# Main.net
KiCad netlist of a schematic drawn in Altium Designer
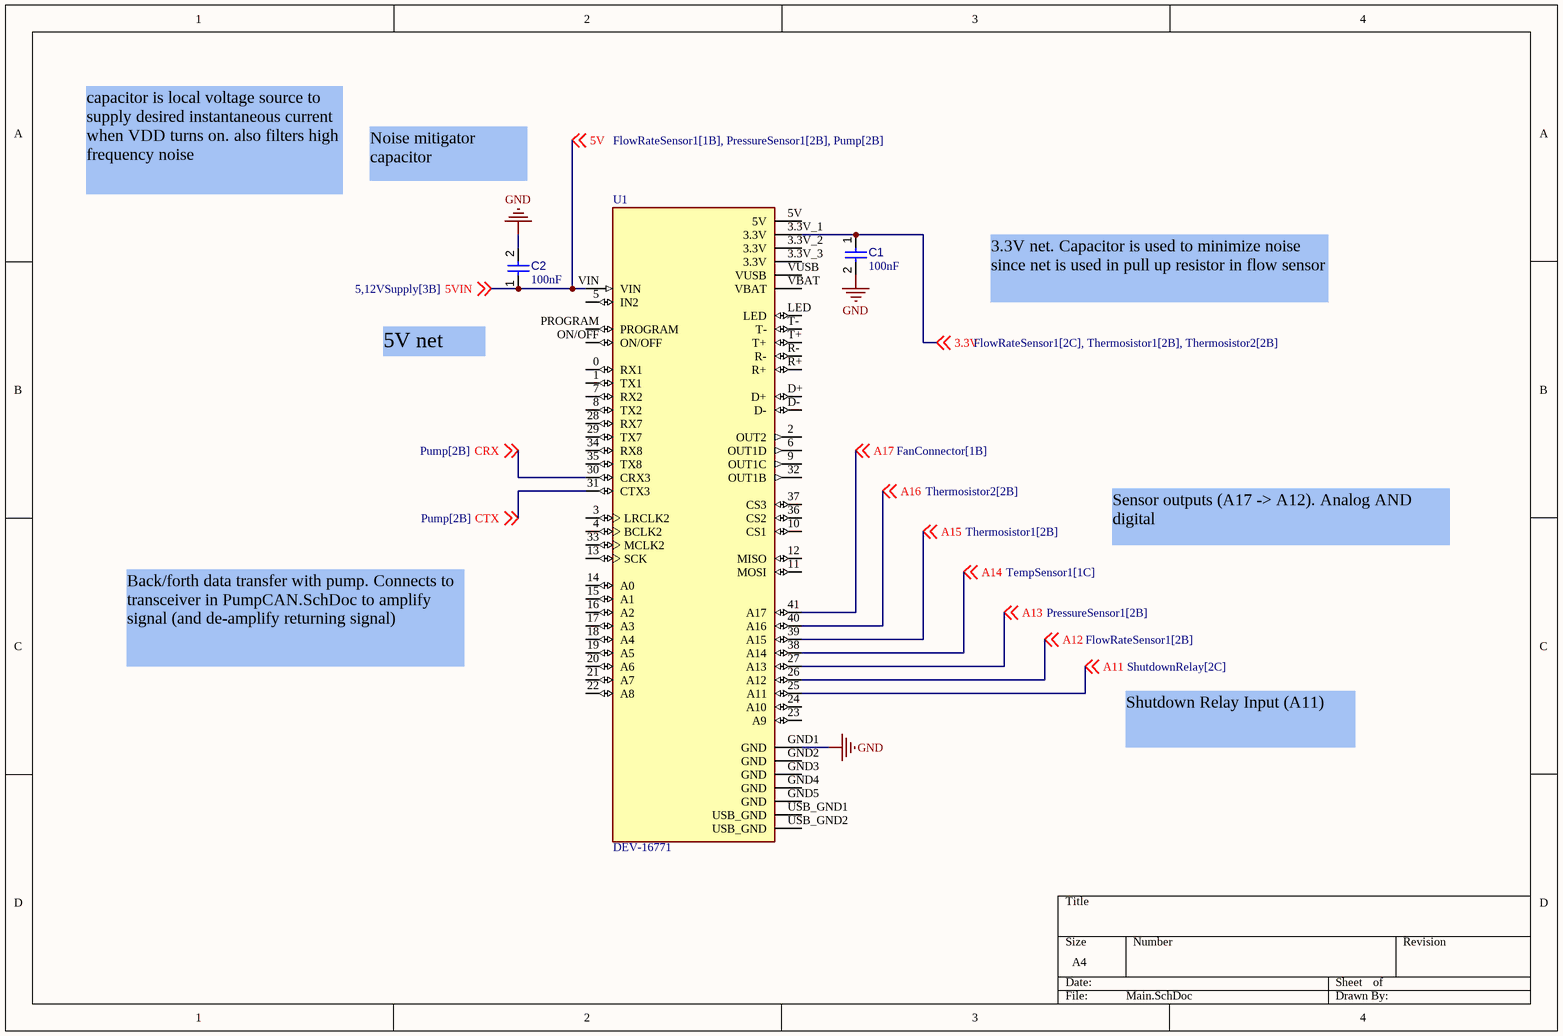
[diagram p0: Main.SchDoc]

(export (version "E")
  (design (tool "Eeschema 10.0.6"))
  (components
    (comp (ref "C1")
      (value "100nF")
      (footprint "CAPC1005X56X25LL10T15")
      (description "Chip Capacitor, 0.1 uF, +/- 5%, 16 V, 0402 (1005 Metric)")
      (fields (field (name "TOLERANCE") "5%") (field (name "Comment") "Capacitor 0.1 uF +/- 5% 16 V 0402"))
      (libsource (lib "Alt_ium Course") (part "CAP-NP-2"))
    )
    (comp (ref "C2")
      (value "100nF")
      (footprint "CAPC1005X56X25LL10T15")
      (description "Chip Capacitor, 0.1 uF, +/- 5%, 16 V, 0402 (1005 Metric)")
      (fields (field (name "TOLERANCE") "5%") (field (name "Comment") "Capacitor 0.1 uF +/- 5% 16 V 0402"))
      (libsource (lib "Alt_ium Course") (part "CAP-NP-2"))
    )
    (comp (ref "U1")
      (value "DEV-16771")
      (footprint "MODULE_DEV-16771")
      (description "RT1062 Teensy 4.1 series ARM® Cortex®-M7 MPU Embedded Evaluation Board")
      (fields (field (name "MF") "SparkFun Electronics"))
      (libsource (lib "Alt_ium Course") (part "DEV-16771"))
    )
  )
  (nets
    (net (code "1") (name "3.3V") (class "Default")
      (node (ref "C1") (pin "1") (pinfunction "1_1") (pintype "passive"))
      (node (ref "U1") (pin "3.3V_1") (pinfunction "3.3V_3.3V_1") (pintype "power_in"))
    )
    (net (code "2") (name "5V") (class "Default")
      (node (ref "C2") (pin "1") (pinfunction "1_1") (pintype "passive"))
      (node (ref "U1") (pin "VIN") (pinfunction "VIN_VIN") (pintype "input"))
    )
    (net (code "3") (name "A11") (class "Default")
      (node (ref "U1") (pin "25") (pinfunction "A11_25") (pintype "bidirectional"))
    )
    (net (code "4") (name "A12") (class "Default")
      (node (ref "U1") (pin "26") (pinfunction "A12_26") (pintype "bidirectional"))
    )
    (net (code "5") (name "A13") (class "Default")
      (node (ref "U1") (pin "27") (pinfunction "A13_27") (pintype "bidirectional"))
    )
    (net (code "6") (name "A14") (class "Default")
      (node (ref "U1") (pin "38") (pinfunction "A14_38") (pintype "bidirectional"))
    )
    (net (code "7") (name "A15") (class "Default")
      (node (ref "U1") (pin "39") (pinfunction "A15_39") (pintype "bidirectional"))
    )
    (net (code "8") (name "A16") (class "Default")
      (node (ref "U1") (pin "40") (pinfunction "A16_40") (pintype "bidirectional"))
    )
    (net (code "9") (name "A17") (class "Default")
      (node (ref "U1") (pin "41") (pinfunction "A17_41") (pintype "bidirectional"))
    )
    (net (code "10") (name "CRX") (class "Default")
      (node (ref "U1") (pin "30") (pinfunction "CRX3_30") (pintype "bidirectional"))
    )
    (net (code "11") (name "CTX") (class "Default")
      (node (ref "U1") (pin "31") (pinfunction "CTX3_31") (pintype "bidirectional"))
    )
    (net (code "12") (name "GND") (class "Default")
      (node (ref "C1") (pin "2") (pinfunction "2_2") (pintype "passive"))
      (node (ref "C2") (pin "2") (pinfunction "2_2") (pintype "passive"))
      (node (ref "U1") (pin "GND1") (pinfunction "GND_GND1") (pintype "power_in"))
    )
    (net (code "13") (name "unconnected-(U1-3.3V-Pad3.3V_2)") (class "Default")
      (node (ref "U1") (pin "3.3V_2") (pinfunction "3.3V_3.3V_2") (pintype "power_in"))
    )
    (net (code "14") (name "unconnected-(U1-3.3V-Pad3.3V_3)") (class "Default")
      (node (ref "U1") (pin "3.3V_3") (pinfunction "3.3V_3.3V_3") (pintype "power_in"))
    )
    (net (code "15") (name "unconnected-(U1-A0-Pad14)") (class "Default")
      (node (ref "U1") (pin "14") (pinfunction "A0_14") (pintype "bidirectional"))
    )
    (net (code "16") (name "unconnected-(U1-A1-Pad15)") (class "Default")
      (node (ref "U1") (pin "15") (pinfunction "A1_15") (pintype "bidirectional"))
    )
    (net (code "17") (name "unconnected-(U1-A2-Pad16)") (class "Default")
      (node (ref "U1") (pin "16") (pinfunction "A2_16") (pintype "bidirectional"))
    )
    (net (code "18") (name "unconnected-(U1-A3-Pad17)") (class "Default")
      (node (ref "U1") (pin "17") (pinfunction "A3_17") (pintype "bidirectional"))
    )
    (net (code "19") (name "unconnected-(U1-A4-Pad18)") (class "Default")
      (node (ref "U1") (pin "18") (pinfunction "A4_18") (pintype "bidirectional"))
    )
    (net (code "20") (name "unconnected-(U1-A5-Pad19)") (class "Default")
      (node (ref "U1") (pin "19") (pinfunction "A5_19") (pintype "bidirectional"))
    )
    (net (code "21") (name "unconnected-(U1-A6-Pad20)") (class "Default")
      (node (ref "U1") (pin "20") (pinfunction "A6_20") (pintype "bidirectional"))
    )
    (net (code "22") (name "unconnected-(U1-A7-Pad21)") (class "Default")
      (node (ref "U1") (pin "21") (pinfunction "A7_21") (pintype "bidirectional"))
    )
    (net (code "23") (name "unconnected-(U1-A8-Pad22)") (class "Default")
      (node (ref "U1") (pin "22") (pinfunction "A8_22") (pintype "bidirectional"))
    )
    (net (code "24") (name "unconnected-(U1-A9-Pad23)") (class "Default")
      (node (ref "U1") (pin "23") (pinfunction "A9_23") (pintype "bidirectional"))
    )
    (net (code "25") (name "unconnected-(U1-A10-Pad24)") (class "Default")
      (node (ref "U1") (pin "24") (pinfunction "A10_24") (pintype "bidirectional"))
    )
    (net (code "26") (name "unconnected-(U1-BCLK2-Pad4)") (class "Default")
      (node (ref "U1") (pin "4") (pinfunction "BCLK2_4") (pintype "bidirectional"))
    )
    (net (code "27") (name "unconnected-(U1-CS1-Pad10)") (class "Default")
      (node (ref "U1") (pin "10") (pinfunction "CS1_10") (pintype "bidirectional"))
    )
    (net (code "28") (name "unconnected-(U1-CS2-Pad36)") (class "Default")
      (node (ref "U1") (pin "36") (pinfunction "CS2_36") (pintype "bidirectional"))
    )
    (net (code "29") (name "unconnected-(U1-CS3-Pad37)") (class "Default")
      (node (ref "U1") (pin "37") (pinfunction "CS3_37") (pintype "bidirectional"))
    )
    (net (code "30") (name "unconnected-(U1-GND-PadGND2)") (class "Default")
      (node (ref "U1") (pin "GND2") (pinfunction "GND_GND2") (pintype "power_in"))
    )
    (net (code "31") (name "unconnected-(U1-GND-PadGND3)") (class "Default")
      (node (ref "U1") (pin "GND3") (pinfunction "GND_GND3") (pintype "power_in"))
    )
    (net (code "32") (name "unconnected-(U1-GND-PadGND4)") (class "Default")
      (node (ref "U1") (pin "GND4") (pinfunction "GND_GND4") (pintype "power_in"))
    )
    (net (code "33") (name "unconnected-(U1-GND-PadGND5)") (class "Default")
      (node (ref "U1") (pin "GND5") (pinfunction "GND_GND5") (pintype "power_in"))
    )
    (net (code "34") (name "unconnected-(U1-IN2-Pad5)") (class "Default")
      (node (ref "U1") (pin "5") (pinfunction "IN2_5") (pintype "bidirectional"))
    )
    (net (code "35") (name "unconnected-(U1-LRCLK2-Pad3)") (class "Default")
      (node (ref "U1") (pin "3") (pinfunction "LRCLK2_3") (pintype "bidirectional"))
    )
    (net (code "36") (name "unconnected-(U1-MCLK2-Pad33)") (class "Default")
      (node (ref "U1") (pin "33") (pinfunction "MCLK2_33") (pintype "bidirectional"))
    )
    (net (code "37") (name "unconnected-(U1-MISO-Pad12)") (class "Default")
      (node (ref "U1") (pin "12") (pinfunction "MISO_12") (pintype "bidirectional"))
    )
    (net (code "38") (name "unconnected-(U1-MOSI-Pad11)") (class "Default")
      (node (ref "U1") (pin "11") (pinfunction "MOSI_11") (pintype "bidirectional"))
    )
    (net (code "39") (name "unconnected-(U1-OUT1B-Pad32)") (class "Default")
      (node (ref "U1") (pin "32") (pinfunction "OUT1B_32") (pintype "output"))
    )
    (net (code "40") (name "unconnected-(U1-OUT1C-Pad9)") (class "Default")
      (node (ref "U1") (pin "9") (pinfunction "OUT1C_9") (pintype "output"))
    )
    (net (code "41") (name "unconnected-(U1-OUT1D-Pad6)") (class "Default")
      (node (ref "U1") (pin "6") (pinfunction "OUT1D_6") (pintype "output"))
    )
    (net (code "42") (name "unconnected-(U1-OUT2-Pad2)") (class "Default")
      (node (ref "U1") (pin "2") (pinfunction "OUT2_2") (pintype "output"))
    )
    (net (code "43") (name "unconnected-(U1-Pad5V)") (class "Default")
      (node (ref "U1") (pin "5V") (pinfunction "5V_5V") (pintype "power_in"))
    )
    (net (code "44") (name "unconnected-(U1-PadD+)") (class "Default")
      (node (ref "U1") (pin "D+") (pinfunction "D+_D+") (pintype "bidirectional"))
    )
    (net (code "45") (name "unconnected-(U1-PadD-)") (class "Default")
      (node (ref "U1") (pin "D-") (pinfunction "D-_D-") (pintype "bidirectional"))
    )
    (net (code "46") (name "unconnected-(U1-PadLED)") (class "Default")
      (node (ref "U1") (pin "LED") (pinfunction "LED_LED") (pintype "bidirectional"))
    )
    (net (code "47") (name "unconnected-(U1-PadON{slash}OFF)") (class "Default")
      (node (ref "U1") (pin "ON/OFF") (pinfunction "ON/OFF_ON/OFF") (pintype "bidirectional"))
    )
    (net (code "48") (name "unconnected-(U1-PadPROGRAM)") (class "Default")
      (node (ref "U1") (pin "PROGRAM") (pinfunction "PROGRAM_PROGRAM") (pintype "bidirectional"))
    )
    (net (code "49") (name "unconnected-(U1-PadR+)") (class "Default")
      (node (ref "U1") (pin "R+") (pinfunction "R+_R+") (pintype "bidirectional"))
    )
    (net (code "50") (name "unconnected-(U1-PadR-)") (class "Default")
      (node (ref "U1") (pin "R-") (pinfunction "R-_R-") (pintype "bidirectional"))
    )
    (net (code "51") (name "unconnected-(U1-PadT+)") (class "Default")
      (node (ref "U1") (pin "T+") (pinfunction "T+_T+") (pintype "bidirectional"))
    )
    (net (code "52") (name "unconnected-(U1-PadT-)") (class "Default")
      (node (ref "U1") (pin "T-") (pinfunction "T-_T-") (pintype "bidirectional"))
    )
    (net (code "53") (name "unconnected-(U1-PadVBAT)") (class "Default")
      (node (ref "U1") (pin "VBAT") (pinfunction "VBAT_VBAT") (pintype "passive"))
    )
    (net (code "54") (name "unconnected-(U1-PadVUSB)") (class "Default")
      (node (ref "U1") (pin "VUSB") (pinfunction "VUSB_VUSB") (pintype "passive"))
    )
    (net (code "55") (name "unconnected-(U1-RX1-Pad0)") (class "Default")
      (node (ref "U1") (pin "0") (pinfunction "RX1_0") (pintype "bidirectional"))
    )
    (net (code "56") (name "unconnected-(U1-RX2-Pad7)") (class "Default")
      (node (ref "U1") (pin "7") (pinfunction "RX2_7") (pintype "bidirectional"))
    )
    (net (code "57") (name "unconnected-(U1-RX7-Pad28)") (class "Default")
      (node (ref "U1") (pin "28") (pinfunction "RX7_28") (pintype "bidirectional"))
    )
    (net (code "58") (name "unconnected-(U1-RX8-Pad34)") (class "Default")
      (node (ref "U1") (pin "34") (pinfunction "RX8_34") (pintype "bidirectional"))
    )
    (net (code "59") (name "unconnected-(U1-SCK-Pad13)") (class "Default")
      (node (ref "U1") (pin "13") (pinfunction "SCK_13") (pintype "bidirectional"))
    )
    (net (code "60") (name "unconnected-(U1-TX1-Pad1)") (class "Default")
      (node (ref "U1") (pin "1") (pinfunction "TX1_1") (pintype "bidirectional"))
    )
    (net (code "61") (name "unconnected-(U1-TX2-Pad8)") (class "Default")
      (node (ref "U1") (pin "8") (pinfunction "TX2_8") (pintype "bidirectional"))
    )
    (net (code "62") (name "unconnected-(U1-TX7-Pad29)") (class "Default")
      (node (ref "U1") (pin "29") (pinfunction "TX7_29") (pintype "bidirectional"))
    )
    (net (code "63") (name "unconnected-(U1-TX8-Pad35)") (class "Default")
      (node (ref "U1") (pin "35") (pinfunction "TX8_35") (pintype "bidirectional"))
    )
    (net (code "64") (name "unconnected-(U1-USB_GND-PadUSB_GND1)") (class "Default")
      (node (ref "U1") (pin "USB_GND1") (pinfunction "USB_GND_USB_GND1") (pintype "power_in"))
    )
    (net (code "65") (name "unconnected-(U1-USB_GND-PadUSB_GND2)") (class "Default")
      (node (ref "U1") (pin "USB_GND2") (pinfunction "USB_GND_USB_GND2") (pintype "power_in"))
    )
  )
)
